# Castle_2_3_2_082224.net
KiCad netlist of a schematic drawn in EAGLE
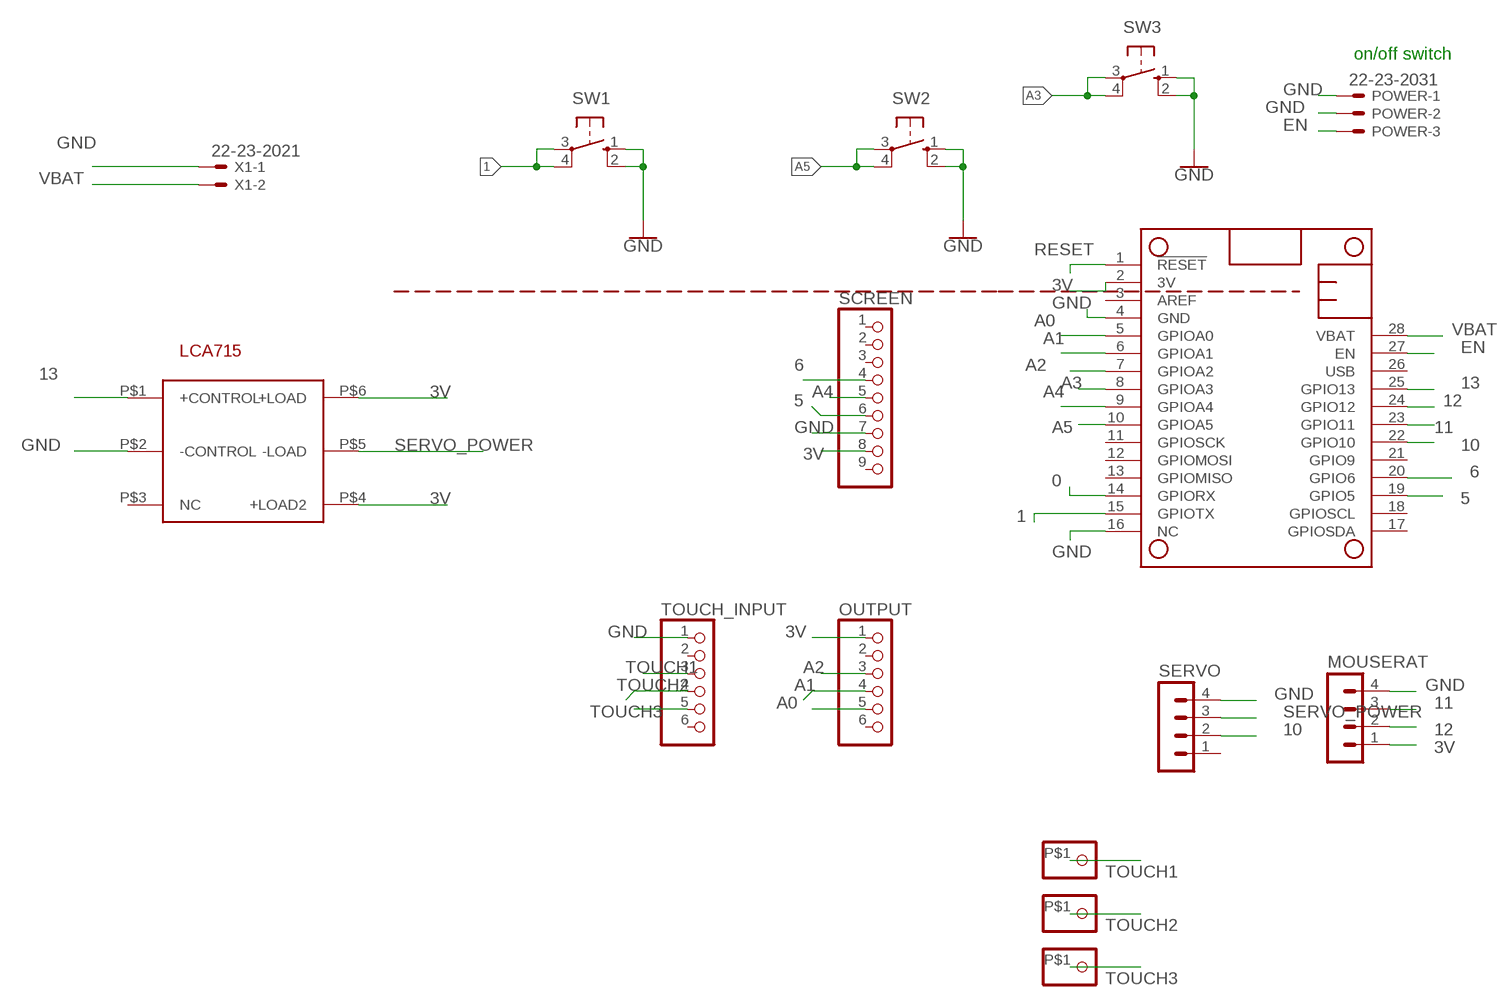
[diagram p0: schematic, sheet 1]

(export (version "E")
  (design (tool "Eeschema 10.0.6"))
  (components
    (comp (ref "EXTRAGND")
      (value "PINHD-1X1-BIGPOGO")
      (footprint "eagle-import:1X1-BIGPOGO")
      (libsource (lib "eagle-import") (part "PINHD-1X1-BIGPOGO"))
    )
    (comp (ref "EXTRAGND1")
      (value "PINHD-1X1-BIGPOGO")
      (footprint "eagle-import:1X1-BIGPOGO")
      (libsource (lib "eagle-import") (part "PINHD-1X1-BIGPOGO"))
    )
    (comp (ref "EXTRAGND2")
      (value "PINHD-1X1-BIGPOGO")
      (footprint "eagle-import:1X1-BIGPOGO")
      (libsource (lib "eagle-import") (part "PINHD-1X1-BIGPOGO"))
    )
    (comp (ref "LCA715")
      (value "LCA715S")
      (footprint "eagle-import:LCA7XX")
      (libsource (lib "eagle-import") (part "LCA715S"))
    )
    (comp (ref "MOUSERAT")
      (value "MA04-1")
      (footprint "eagle-import:MA04-1")
      (libsource (lib "eagle-import") (part "MA04-1"))
    )
    (comp (ref "MS2")
      (value "FEATHERWING_NODIM")
      (footprint "eagle-import:FEATHERWING_DIM")
      (libsource (lib "eagle-import") (part "FEATHERWING_NODIM"))
    )
    (comp (ref "OUTPUT")
      (value "PINHD-1X6")
      (footprint "eagle-import:1X06")
      (libsource (lib "eagle-import") (part "PINHD-1X6"))
    )
    (comp (ref "POWER")
      (value "22-23-2031")
      (footprint "eagle-import:22-23-2031")
      (fields (field (name "MF") "MOLEX"))
      (libsource (lib "eagle-import") (part "22-23-2031"))
    )
    (comp (ref "SCREEN")
      (value "PINHD-1X9")
      (footprint "eagle-import:1X09-BIG")
      (libsource (lib "eagle-import") (part "PINHD-1X9"))
    )
    (comp (ref "SERVO")
      (value "MA04-1")
      (footprint "eagle-import:MA04-1")
      (libsource (lib "eagle-import") (part "MA04-1"))
    )
    (comp (ref "SW1")
      (value "10-XX")
      (footprint "eagle-import:B3F-10XX")
      (libsource (lib "eagle-import") (part "10-XX"))
    )
    (comp (ref "SW2")
      (value "10-XX")
      (footprint "eagle-import:B3F-10XX")
      (libsource (lib "eagle-import") (part "10-XX"))
    )
    (comp (ref "SW3")
      (value "10-XX")
      (footprint "eagle-import:B3F-10XX")
      (libsource (lib "eagle-import") (part "10-XX"))
    )
    (comp (ref "TOUCH_INPUT")
      (value "PINHD-1X6")
      (footprint "eagle-import:1X06")
      (libsource (lib "eagle-import") (part "PINHD-1X6"))
    )
    (comp (ref "X1")
      (value "22-23-2021")
      (footprint "eagle-import:22-23-2021")
      (fields (field (name "MF") "MOLEX"))
      (libsource (lib "eagle-import") (part "22-23-2021"))
    )
  )
  (nets
    (net (code "1") (name "/0") (class "Default")
      (node (ref "MS2") (pin "14") (pinfunction "GPIORX_14") (pintype "bidirectional"))
    )
    (net (code "2") (name "/3V") (class "Default")
      (node (ref "LCA715") (pin "P$4") (pinfunction "+LOAD2_P$4") (pintype "bidirectional"))
      (node (ref "LCA715") (pin "P$6") (pinfunction "+LOAD_P$6") (pintype "bidirectional"))
      (node (ref "MOUSERAT") (pin "1") (pinfunction "1_1") (pintype "passive"))
      (node (ref "MS2") (pin "2") (pinfunction "3V_2") (pintype "power_in"))
      (node (ref "OUTPUT") (pin "1") (pinfunction "1_1") (pintype "passive"))
      (node (ref "SCREEN") (pin "8") (pinfunction "8_8") (pintype "passive"))
    )
    (net (code "3") (name "/5") (class "Default")
      (node (ref "MS2") (pin "19") (pinfunction "GPIO5_19") (pintype "bidirectional"))
      (node (ref "SCREEN") (pin "6") (pinfunction "6_6") (pintype "passive"))
    )
    (net (code "4") (name "/6") (class "Default")
      (node (ref "MS2") (pin "20") (pinfunction "GPIO6_20") (pintype "bidirectional"))
      (node (ref "SCREEN") (pin "4") (pinfunction "4_4") (pintype "passive"))
    )
    (net (code "5") (name "/10") (class "Default")
      (node (ref "MS2") (pin "22") (pinfunction "GPIO10_22") (pintype "bidirectional"))
      (node (ref "SERVO") (pin "2") (pinfunction "2_2") (pintype "passive"))
    )
    (net (code "6") (name "/11") (class "Default")
      (node (ref "MOUSERAT") (pin "3") (pinfunction "3_3") (pintype "passive"))
      (node (ref "MS2") (pin "23") (pinfunction "GPIO11_23") (pintype "bidirectional"))
    )
    (net (code "7") (name "/12") (class "Default")
      (node (ref "MOUSERAT") (pin "2") (pinfunction "2_2") (pintype "passive"))
      (node (ref "MS2") (pin "24") (pinfunction "GPIO12_24") (pintype "bidirectional"))
    )
    (net (code "8") (name "/13") (class "Default")
      (node (ref "LCA715") (pin "P$1") (pinfunction "+CONTROL_P$1") (pintype "bidirectional"))
      (node (ref "MS2") (pin "25") (pinfunction "GPIO13_25") (pintype "bidirectional"))
    )
    (net (code "9") (name "/A0") (class "Default")
      (node (ref "MS2") (pin "5") (pinfunction "GPIOA0_5") (pintype "bidirectional"))
      (node (ref "OUTPUT") (pin "5") (pinfunction "5_5") (pintype "passive"))
    )
    (net (code "10") (name "/A1") (class "Default")
      (node (ref "MS2") (pin "6") (pinfunction "GPIOA1_6") (pintype "bidirectional"))
      (node (ref "OUTPUT") (pin "4") (pinfunction "4_4") (pintype "passive"))
    )
    (net (code "11") (name "/A2") (class "Default")
      (node (ref "MS2") (pin "7") (pinfunction "GPIOA2_7") (pintype "bidirectional"))
      (node (ref "OUTPUT") (pin "3") (pinfunction "3_3") (pintype "passive"))
    )
    (net (code "12") (name "/A4") (class "Default")
      (node (ref "MS2") (pin "9") (pinfunction "GPIOA4_9") (pintype "bidirectional"))
      (node (ref "SCREEN") (pin "5") (pinfunction "5_5") (pintype "passive"))
    )
    (net (code "13") (name "/EN") (class "Default")
      (node (ref "MS2") (pin "27") (pinfunction "EN_27") (pintype "passive"))
      (node (ref "POWER") (pin "3") (pinfunction "S_3") (pintype "passive"))
    )
    (net (code "14") (name "/RESET") (class "Default")
      (node (ref "MS2") (pin "1") (pinfunction "~{RESET}_1") (pintype "input"))
    )
    (net (code "15") (name "/SERVO_POWER") (class "Default")
      (node (ref "LCA715") (pin "P$5") (pinfunction "-LOAD_P$5") (pintype "bidirectional"))
      (node (ref "SERVO") (pin "3") (pinfunction "3_3") (pintype "passive"))
    )
    (net (code "16") (name "/TOUCH1") (class "Default")
      (node (ref "EXTRAGND") (pin "P$1") (pinfunction "1_P$1") (pintype "passive"))
      (node (ref "TOUCH_INPUT") (pin "3") (pinfunction "3_3") (pintype "passive"))
    )
    (net (code "17") (name "/TOUCH2") (class "Default")
      (node (ref "EXTRAGND1") (pin "P$1") (pinfunction "1_P$1") (pintype "passive"))
      (node (ref "TOUCH_INPUT") (pin "4") (pinfunction "4_4") (pintype "passive"))
    )
    (net (code "18") (name "/TOUCH3") (class "Default")
      (node (ref "EXTRAGND2") (pin "P$1") (pinfunction "1_P$1") (pintype "passive"))
      (node (ref "TOUCH_INPUT") (pin "5") (pinfunction "5_5") (pintype "passive"))
    )
    (net (code "19") (name "/USB") (class "Default")
      (node (ref "MS2") (pin "26") (pinfunction "USB_26") (pintype "power_in"))
    )
    (net (code "20") (name "/VBAT") (class "Default")
      (node (ref "MS2") (pin "28") (pinfunction "VBAT_28") (pintype "power_in"))
      (node (ref "X1") (pin "2") (pinfunction "S_2") (pintype "passive"))
    )
    (net (code "21") (name "1") (class "Default")
      (node (ref "MS2") (pin "15") (pinfunction "GPIOTX_15") (pintype "bidirectional"))
      (node (ref "SW1") (pin "3") (pinfunction "P_3") (pintype "passive"))
      (node (ref "SW1") (pin "4") (pinfunction "P1_4") (pintype "passive"))
    )
    (net (code "22") (name "A3") (class "Default")
      (node (ref "MS2") (pin "8") (pinfunction "GPIOA3_8") (pintype "bidirectional"))
      (node (ref "SW3") (pin "3") (pinfunction "P_3") (pintype "passive"))
      (node (ref "SW3") (pin "4") (pinfunction "P1_4") (pintype "passive"))
    )
    (net (code "23") (name "A5") (class "Default")
      (node (ref "MS2") (pin "10") (pinfunction "GPIOA5_10") (pintype "bidirectional"))
      (node (ref "SW2") (pin "3") (pinfunction "P_3") (pintype "passive"))
      (node (ref "SW2") (pin "4") (pinfunction "P1_4") (pintype "passive"))
    )
    (net (code "24") (name "GND") (class "Default")
      (node (ref "LCA715") (pin "P$2") (pinfunction "-CONTROL_P$2") (pintype "bidirectional"))
      (node (ref "MOUSERAT") (pin "4") (pinfunction "4_4") (pintype "passive"))
      (node (ref "MS2") (pin "16") (pinfunction "NC_16") (pintype "passive"))
      (node (ref "MS2") (pin "4") (pinfunction "GND_4") (pintype "power_in"))
      (node (ref "POWER") (pin "1") (pinfunction "S_1") (pintype "passive"))
      (node (ref "POWER") (pin "2") (pinfunction "S_2") (pintype "passive"))
      (node (ref "SCREEN") (pin "7") (pinfunction "7_7") (pintype "passive"))
      (node (ref "SERVO") (pin "4") (pinfunction "4_4") (pintype "passive"))
      (node (ref "SW1") (pin "1") (pinfunction "S_1") (pintype "passive"))
      (node (ref "SW1") (pin "2") (pinfunction "S1_2") (pintype "passive"))
      (node (ref "SW2") (pin "1") (pinfunction "S_1") (pintype "passive"))
      (node (ref "SW2") (pin "2") (pinfunction "S1_2") (pintype "passive"))
      (node (ref "SW3") (pin "1") (pinfunction "S_1") (pintype "passive"))
      (node (ref "SW3") (pin "2") (pinfunction "S1_2") (pintype "passive"))
      (node (ref "TOUCH_INPUT") (pin "1") (pinfunction "1_1") (pintype "passive"))
      (node (ref "X1") (pin "1") (pinfunction "S_1") (pintype "passive"))
    )
    (net (code "25") (name "unconnected-(LCA715-NC-PadP$3)") (class "Default")
      (node (ref "LCA715") (pin "P$3") (pinfunction "NC_P$3") (pintype "bidirectional"))
    )
    (net (code "26") (name "unconnected-(MS2-AREF-Pad3)") (class "Default")
      (node (ref "MS2") (pin "3") (pinfunction "AREF_3") (pintype "passive"))
    )
    (net (code "27") (name "unconnected-(MS2-GPIO9-Pad21)") (class "Default")
      (node (ref "MS2") (pin "21") (pinfunction "GPIO9_21") (pintype "bidirectional"))
    )
    (net (code "28") (name "unconnected-(MS2-GPIOMISO-Pad13)") (class "Default")
      (node (ref "MS2") (pin "13") (pinfunction "GPIOMISO_13") (pintype "bidirectional"))
    )
    (net (code "29") (name "unconnected-(MS2-GPIOMOSI-Pad12)") (class "Default")
      (node (ref "MS2") (pin "12") (pinfunction "GPIOMOSI_12") (pintype "bidirectional"))
    )
    (net (code "30") (name "unconnected-(MS2-GPIOSCK-Pad11)") (class "Default")
      (node (ref "MS2") (pin "11") (pinfunction "GPIOSCK_11") (pintype "bidirectional"))
    )
    (net (code "31") (name "unconnected-(MS2-GPIOSCL-Pad18)") (class "Default")
      (node (ref "MS2") (pin "18") (pinfunction "GPIOSCL_18") (pintype "bidirectional"))
    )
    (net (code "32") (name "unconnected-(MS2-GPIOSDA-Pad17)") (class "Default")
      (node (ref "MS2") (pin "17") (pinfunction "GPIOSDA_17") (pintype "bidirectional"))
    )
    (net (code "33") (name "unconnected-(OUTPUT-Pad2)") (class "Default")
      (node (ref "OUTPUT") (pin "2") (pinfunction "2_2") (pintype "passive"))
    )
    (net (code "34") (name "unconnected-(OUTPUT-Pad6)") (class "Default")
      (node (ref "OUTPUT") (pin "6") (pinfunction "6_6") (pintype "passive"))
    )
    (net (code "35") (name "unconnected-(SCREEN-Pad1)") (class "Default")
      (node (ref "SCREEN") (pin "1") (pinfunction "1_1") (pintype "passive"))
    )
    (net (code "36") (name "unconnected-(SCREEN-Pad2)") (class "Default")
      (node (ref "SCREEN") (pin "2") (pinfunction "2_2") (pintype "passive"))
    )
    (net (code "37") (name "unconnected-(SCREEN-Pad3)") (class "Default")
      (node (ref "SCREEN") (pin "3") (pinfunction "3_3") (pintype "passive"))
    )
    (net (code "38") (name "unconnected-(SCREEN-Pad9)") (class "Default")
      (node (ref "SCREEN") (pin "9") (pinfunction "9_9") (pintype "passive"))
    )
    (net (code "39") (name "unconnected-(SERVO-Pad1)") (class "Default")
      (node (ref "SERVO") (pin "1") (pinfunction "1_1") (pintype "passive"))
    )
    (net (code "40") (name "unconnected-(TOUCH_INPUT-Pad2)") (class "Default")
      (node (ref "TOUCH_INPUT") (pin "2") (pinfunction "2_2") (pintype "passive"))
    )
    (net (code "41") (name "unconnected-(TOUCH_INPUT-Pad6)") (class "Default")
      (node (ref "TOUCH_INPUT") (pin "6") (pinfunction "6_6") (pintype "passive"))
    )
  )
)
